# 03_MCU.net
KiCad netlist of a schematic drawn in Altium Designer
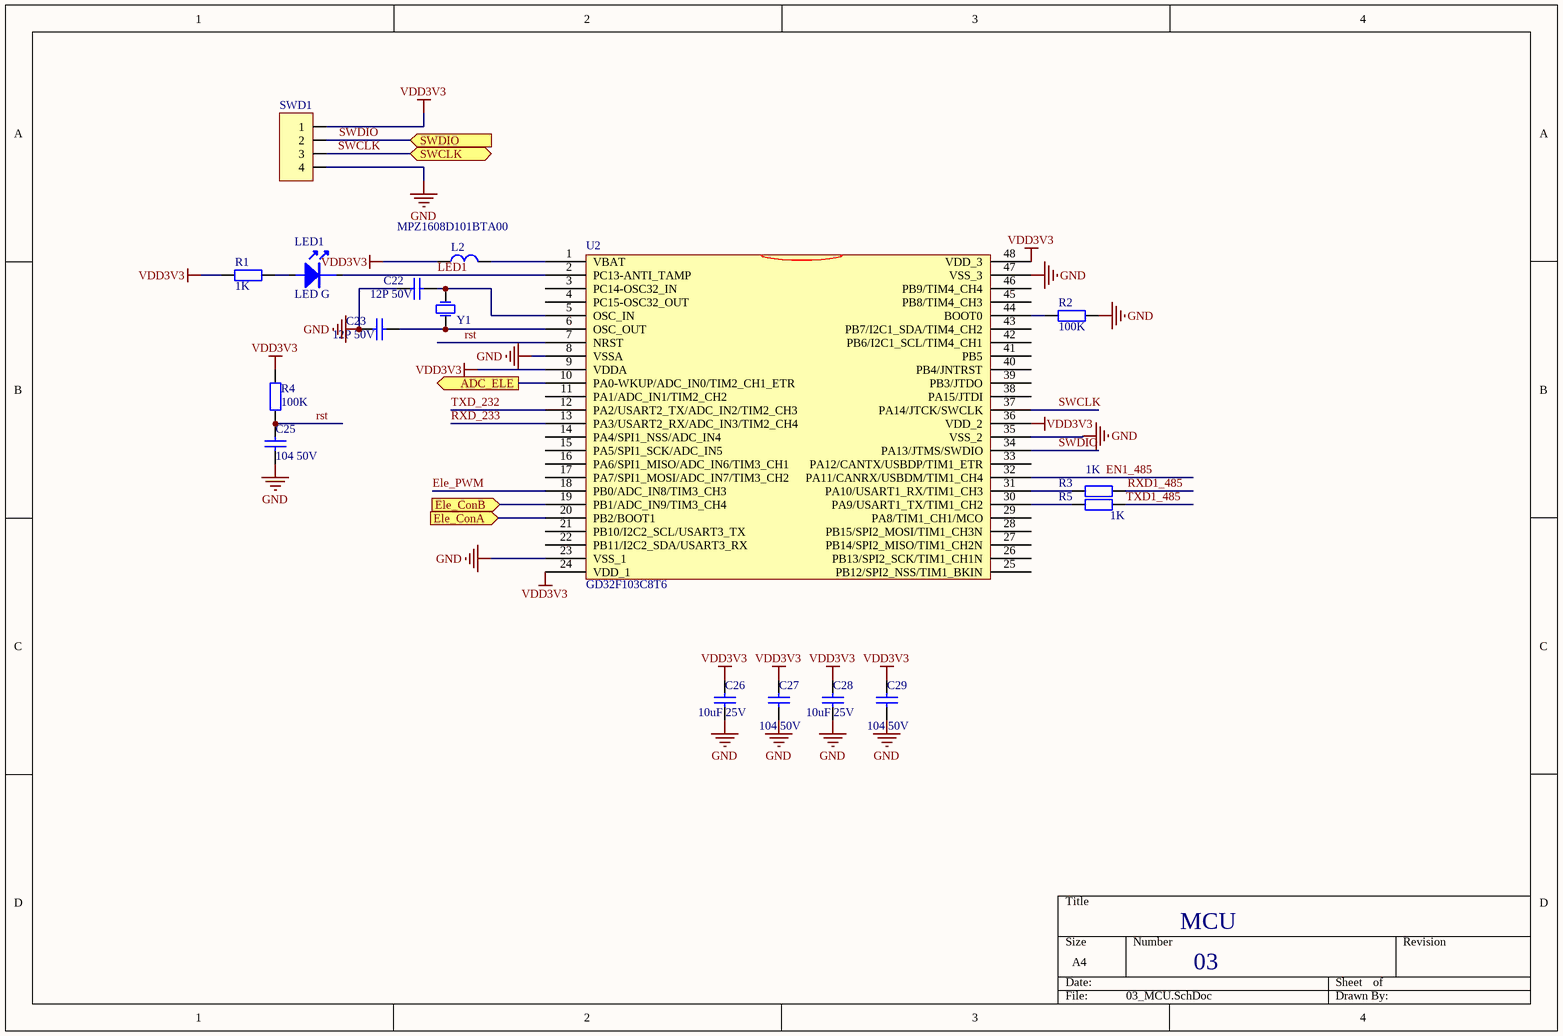
[diagram p0: 03_MCU.SchDoc]

(export (version "E")
  (design (tool "Eeschema 10.0.6"))
  (components
    (comp (ref "C22")
      (value "12P 50V")
      (footprint "SMD-0603C")
      (description "贴片电容 5%")
      (libsource (lib "XiaoyI") (part "CAP4"))
    )
    (comp (ref "C23")
      (value "12P 50V")
      (footprint "SMD-0603C")
      (description "贴片电容 5%")
      (libsource (lib "XiaoyI") (part "CAP4"))
    )
    (comp (ref "C25")
      (value "104 50V")
      (footprint "SMD-0603C")
      (description "贴片电容 20%")
      (libsource (lib "XiaoyI") (part "CAP4"))
    )
    (comp (ref "C26")
      (value "10uF 25V")
      (footprint "SMD-0805C")
      (description "贴片电容 20%")
      (libsource (lib "XiaoyI") (part "CAP4"))
    )
    (comp (ref "C27")
      (value "104 50V")
      (footprint "SMD-0603C")
      (description "贴片电容 20%")
      (libsource (lib "XiaoyI") (part "CAP4"))
    )
    (comp (ref "C28")
      (value "10uF 25V")
      (footprint "SMD-0805C")
      (description "贴片电容 20%")
      (libsource (lib "XiaoyI") (part "CAP4"))
    )
    (comp (ref "C29")
      (value "104 50V")
      (footprint "SMD-0603C")
      (description "贴片电容 20%")
      (libsource (lib "XiaoyI") (part "CAP4"))
    )
    (comp (ref "L2")
      (value "MPZ1608D101BTA00")
      (footprint "SMD-0603")
      (description "磁珠电感 100R 100MHz")
      (libsource (lib "XiaoyI") (part "CIZHU1"))
    )
    (comp (ref "LED1")
      (value "LED G")
      (footprint "SMD-0603D")
      (description "绿色普亮")
      (libsource (lib "ABB") (part "LED"))
    )
    (comp (ref "R1")
      (value "1K")
      (footprint "SMD-0603")
      (description "贴片电阻 5%")
      (libsource (lib "ABB") (part "RES0"))
    )
    (comp (ref "R2")
      (value "100K")
      (footprint "SMD-0603")
      (description "贴片电阻 5%")
      (libsource (lib "") (part "RES2_1"))
    )
    (comp (ref "R3")
      (value "1K")
      (footprint "SMD-0603")
      (description "贴片电阻 5%")
      (libsource (lib "") (part "RES2_1"))
    )
    (comp (ref "R4")
      (value "100K")
      (footprint "SMD-0603")
      (description "贴片电阻 5%")
      (libsource (lib "XiaoyI") (part "RES2"))
    )
    (comp (ref "R5")
      (value "1K")
      (footprint "SMD-0603")
      (description "贴片电阻 5%")
      (libsource (lib "") (part "RES2_1"))
    )
    (comp (ref "SWD1")
      (value "SIP-4 (NC)")
      (footprint "SIP-4")
      (description "ISP 下载")
      (libsource (lib "XiaoyI") (part "SIP-4"))
    )
    (comp (ref "U2")
      (value "GD32F103C8T6")
      (footprint "LQFP48")
      (libsource (lib "stm32") (part "STM32F103C6"))
    )
    (comp (ref "Y1")
      (value "8MHz")
      (footprint "XTAL-3225-2")
      (description "3225 贴片晶振")
      (libsource (lib "XiaoyI") (part "XTAL"))
    )
  )
  (nets
    (net (code "1") (name "/ADC_ELE") (class "Default")
      (node (ref "U2") (pin "10") (pinfunction "PA0-WKUP/ADC_IN0/TIM2_CH1_ETR_10") (pintype "passive"))
    )
    (net (code "2") (name "/EN1_485") (class "Default")
      (node (ref "U2") (pin "32") (pinfunction "PA11/CANRX/USBDM/TIM1_CH4_32") (pintype "passive"))
    )
    (net (code "3") (name "/Ele_ConA") (class "Default")
      (node (ref "U2") (pin "20") (pinfunction "PB2/BOOT1_20") (pintype "passive"))
    )
    (net (code "4") (name "/Ele_ConB") (class "Default")
      (node (ref "U2") (pin "19") (pinfunction "PB1/ADC_IN9/TIM3_CH4_19") (pintype "passive"))
    )
    (net (code "5") (name "/Ele_PWM") (class "Default")
      (node (ref "U2") (pin "18") (pinfunction "PB0/ADC_IN8/TIM3_CH3_18") (pintype "passive"))
    )
    (net (code "6") (name "/LED1") (class "Default")
      (node (ref "LED1") (pin "2") (pinfunction "K_2") (pintype "passive"))
      (node (ref "U2") (pin "2") (pinfunction "PC13-ANTI_TAMP_2") (pintype "passive"))
    )
    (net (code "7") (name "/RXD1_485") (class "Default")
      (node (ref "R3") (pin "2") (pinfunction "2_2") (pintype "passive"))
    )
    (net (code "8") (name "/RXD_233") (class "Default")
      (node (ref "U2") (pin "13") (pinfunction "PA3/USART2_RX/ADC_IN3/TIM2_CH4_13") (pintype "passive"))
    )
    (net (code "9") (name "/SWCLK") (class "Default")
      (node (ref "SWD1") (pin "3") (pinfunction "3_3") (pintype "passive"))
      (node (ref "U2") (pin "37") (pinfunction "PA14/JTCK/SWCLK_37") (pintype "passive"))
    )
    (net (code "10") (name "/SWDIO") (class "Default")
      (node (ref "SWD1") (pin "2") (pinfunction "2_2") (pintype "passive"))
      (node (ref "U2") (pin "34") (pinfunction "PA13/JTMS/SWDIO_34") (pintype "passive"))
    )
    (net (code "11") (name "/TXD1_485") (class "Default")
      (node (ref "R5") (pin "2") (pinfunction "2_2") (pintype "passive"))
    )
    (net (code "12") (name "/TXD_232") (class "Default")
      (node (ref "U2") (pin "12") (pinfunction "PA2/USART2_TX/ADC_IN2/TIM2_CH3_12") (pintype "passive"))
    )
    (net (code "13") (name "/rst") (class "Default")
      (node (ref "C25") (pin "2") (pinfunction "2_2") (pintype "passive"))
      (node (ref "R4") (pin "2") (pinfunction "2_2") (pintype "passive"))
      (node (ref "U2") (pin "7") (pinfunction "NRST_7") (pintype "passive"))
    )
    (net (code "14") (name "GND") (class "Default")
      (node (ref "C22") (pin "2") (pinfunction "2_2") (pintype "passive"))
      (node (ref "C23") (pin "2") (pinfunction "2_2") (pintype "passive"))
      (node (ref "C25") (pin "1") (pinfunction "1_1") (pintype "passive"))
      (node (ref "C26") (pin "1") (pinfunction "1_1") (pintype "passive"))
      (node (ref "C27") (pin "1") (pinfunction "1_1") (pintype "passive"))
      (node (ref "C28") (pin "1") (pinfunction "1_1") (pintype "passive"))
      (node (ref "C29") (pin "1") (pinfunction "1_1") (pintype "passive"))
      (node (ref "R2") (pin "2") (pinfunction "2_2") (pintype "passive"))
      (node (ref "SWD1") (pin "4") (pinfunction "4_4") (pintype "passive"))
      (node (ref "U2") (pin "23") (pinfunction "VSS_1_23") (pintype "passive"))
      (node (ref "U2") (pin "35") (pinfunction "VSS_2_35") (pintype "passive"))
      (node (ref "U2") (pin "47") (pinfunction "VSS_3_47") (pintype "passive"))
      (node (ref "U2") (pin "8") (pinfunction "VSSA_8") (pintype "passive"))
    )
    (net (code "15") (name "Net-(LED1-A)") (class "Default")
      (node (ref "LED1") (pin "1") (pinfunction "A_1") (pintype "passive"))
      (node (ref "R1") (pin "1") (pinfunction "1_1") (pintype "passive"))
    )
    (net (code "16") (name "Net-(U2-BOOT0)") (class "Default")
      (node (ref "R2") (pin "1") (pinfunction "1_1") (pintype "passive"))
      (node (ref "U2") (pin "44") (pinfunction "BOOT0_44") (pintype "passive"))
    )
    (net (code "17") (name "Net-(U2-OSC_IN)") (class "Default")
      (node (ref "C22") (pin "1") (pinfunction "1_1") (pintype "passive"))
      (node (ref "U2") (pin "5") (pinfunction "OSC_IN_5") (pintype "passive"))
      (node (ref "Y1") (pin "1") (pinfunction "OSC1_1") (pintype "passive"))
    )
    (net (code "18") (name "Net-(U2-OSC_OUT)") (class "Default")
      (node (ref "C23") (pin "1") (pinfunction "1_1") (pintype "passive"))
      (node (ref "U2") (pin "6") (pinfunction "OSC_OUT_6") (pintype "passive"))
      (node (ref "Y1") (pin "2") (pinfunction "OSC2_2") (pintype "passive"))
    )
    (net (code "19") (name "Net-(U2-PA9{slash}USART1_TX{slash}TIM1_CH2)") (class "Default")
      (node (ref "R5") (pin "1") (pinfunction "1_1") (pintype "passive"))
      (node (ref "U2") (pin "30") (pinfunction "PA9/USART1_TX/TIM1_CH2_30") (pintype "passive"))
    )
    (net (code "20") (name "Net-(U2-PA10{slash}USART1_RX{slash}TIM1_CH3)") (class "Default")
      (node (ref "R3") (pin "1") (pinfunction "1_1") (pintype "passive"))
      (node (ref "U2") (pin "31") (pinfunction "PA10/USART1_RX/TIM1_CH3_31") (pintype "passive"))
    )
    (net (code "21") (name "Net-(U2-VBAT)") (class "Default")
      (node (ref "L2") (pin "1") (pinfunction "1_1") (pintype "passive"))
      (node (ref "U2") (pin "1") (pinfunction "VBAT_1") (pintype "passive"))
    )
    (net (code "22") (name "VDD3V3") (class "Default")
      (node (ref "C26") (pin "2") (pinfunction "2_2") (pintype "passive"))
      (node (ref "C27") (pin "2") (pinfunction "2_2") (pintype "passive"))
      (node (ref "C28") (pin "2") (pinfunction "2_2") (pintype "passive"))
      (node (ref "C29") (pin "2") (pinfunction "2_2") (pintype "passive"))
      (node (ref "L2") (pin "2") (pinfunction "2_2") (pintype "passive"))
      (node (ref "R1") (pin "2") (pinfunction "2_2") (pintype "passive"))
      (node (ref "R4") (pin "1") (pinfunction "1_1") (pintype "passive"))
      (node (ref "SWD1") (pin "1") (pinfunction "1_1") (pintype "passive"))
      (node (ref "U2") (pin "24") (pinfunction "VDD_1_24") (pintype "passive"))
      (node (ref "U2") (pin "36") (pinfunction "VDD_2_36") (pintype "passive"))
      (node (ref "U2") (pin "48") (pinfunction "VDD_3_48") (pintype "passive"))
      (node (ref "U2") (pin "9") (pinfunction "VDDA_9") (pintype "passive"))
    )
    (net (code "23") (name "unconnected-(U2-PA1{slash}ADC_IN1{slash}TIM2_CH2-Pad11)") (class "Default")
      (node (ref "U2") (pin "11") (pinfunction "PA1/ADC_IN1/TIM2_CH2_11") (pintype "passive"))
    )
    (net (code "24") (name "unconnected-(U2-PA4{slash}SPI1_NSS{slash}ADC_IN4-Pad14)") (class "Default")
      (node (ref "U2") (pin "14") (pinfunction "PA4/SPI1_NSS/ADC_IN4_14") (pintype "passive"))
    )
    (net (code "25") (name "unconnected-(U2-PA5{slash}SPI1_SCK{slash}ADC_IN5-Pad15)") (class "Default")
      (node (ref "U2") (pin "15") (pinfunction "PA5/SPI1_SCK/ADC_IN5_15") (pintype "passive"))
    )
    (net (code "26") (name "unconnected-(U2-PA6{slash}SPI1_MISO{slash}ADC_IN6{slash}TIM3_CH1-Pad16)") (class "Default")
      (node (ref "U2") (pin "16") (pinfunction "PA6/SPI1_MISO/ADC_IN6/TIM3_CH1_16") (pintype "passive"))
    )
    (net (code "27") (name "unconnected-(U2-PA7{slash}SPI1_MOSI{slash}ADC_IN7{slash}TIM3_CH2-Pad17)") (class "Default")
      (node (ref "U2") (pin "17") (pinfunction "PA7/SPI1_MOSI/ADC_IN7/TIM3_CH2_17") (pintype "passive"))
    )
    (net (code "28") (name "unconnected-(U2-PA8{slash}TIM1_CH1{slash}MCO-Pad29)") (class "Default")
      (node (ref "U2") (pin "29") (pinfunction "PA8/TIM1_CH1/MCO_29") (pintype "passive"))
    )
    (net (code "29") (name "unconnected-(U2-PA12{slash}CANTX{slash}USBDP{slash}TIM1_ETR-Pad33)") (class "Default")
      (node (ref "U2") (pin "33") (pinfunction "PA12/CANTX/USBDP/TIM1_ETR_33") (pintype "passive"))
    )
    (net (code "30") (name "unconnected-(U2-PA15{slash}JTDI-Pad38)") (class "Default")
      (node (ref "U2") (pin "38") (pinfunction "PA15/JTDI_38") (pintype "passive"))
    )
    (net (code "31") (name "unconnected-(U2-PB3{slash}JTDO-Pad39)") (class "Default")
      (node (ref "U2") (pin "39") (pinfunction "PB3/JTDO_39") (pintype "passive"))
    )
    (net (code "32") (name "unconnected-(U2-PB4{slash}JNTRST-Pad40)") (class "Default")
      (node (ref "U2") (pin "40") (pinfunction "PB4/JNTRST_40") (pintype "passive"))
    )
    (net (code "33") (name "unconnected-(U2-PB5-Pad41)") (class "Default")
      (node (ref "U2") (pin "41") (pinfunction "PB5_41") (pintype "passive"))
    )
    (net (code "34") (name "unconnected-(U2-PB6{slash}I2C1_SCL{slash}TIM4_CH1-Pad42)") (class "Default")
      (node (ref "U2") (pin "42") (pinfunction "PB6/I2C1_SCL/TIM4_CH1_42") (pintype "passive"))
    )
    (net (code "35") (name "unconnected-(U2-PB7{slash}I2C1_SDA{slash}TIM4_CH2-Pad43)") (class "Default")
      (node (ref "U2") (pin "43") (pinfunction "PB7/I2C1_SDA/TIM4_CH2_43") (pintype "passive"))
    )
    (net (code "36") (name "unconnected-(U2-PB8{slash}TIM4_CH3-Pad45)") (class "Default")
      (node (ref "U2") (pin "45") (pinfunction "PB8/TIM4_CH3_45") (pintype "passive"))
    )
    (net (code "37") (name "unconnected-(U2-PB9{slash}TIM4_CH4-Pad46)") (class "Default")
      (node (ref "U2") (pin "46") (pinfunction "PB9/TIM4_CH4_46") (pintype "passive"))
    )
    (net (code "38") (name "unconnected-(U2-PB10{slash}I2C2_SCL{slash}USART3_TX-Pad21)") (class "Default")
      (node (ref "U2") (pin "21") (pinfunction "PB10/I2C2_SCL/USART3_TX_21") (pintype "passive"))
    )
    (net (code "39") (name "unconnected-(U2-PB11{slash}I2C2_SDA{slash}USART3_RX-Pad22)") (class "Default")
      (node (ref "U2") (pin "22") (pinfunction "PB11/I2C2_SDA/USART3_RX_22") (pintype "passive"))
    )
    (net (code "40") (name "unconnected-(U2-PB12{slash}SPI2_NSS{slash}TIM1_BKIN-Pad25)") (class "Default")
      (node (ref "U2") (pin "25") (pinfunction "PB12/SPI2_NSS/TIM1_BKIN_25") (pintype "passive"))
    )
    (net (code "41") (name "unconnected-(U2-PB13{slash}SPI2_SCK{slash}TIM1_CH1N-Pad26)") (class "Default")
      (node (ref "U2") (pin "26") (pinfunction "PB13/SPI2_SCK/TIM1_CH1N_26") (pintype "passive"))
    )
    (net (code "42") (name "unconnected-(U2-PB14{slash}SPI2_MISO{slash}TIM1_CH2N-Pad27)") (class "Default")
      (node (ref "U2") (pin "27") (pinfunction "PB14/SPI2_MISO/TIM1_CH2N_27") (pintype "passive"))
    )
    (net (code "43") (name "unconnected-(U2-PB15{slash}SPI2_MOSI{slash}TIM1_CH3N-Pad28)") (class "Default")
      (node (ref "U2") (pin "28") (pinfunction "PB15/SPI2_MOSI/TIM1_CH3N_28") (pintype "passive"))
    )
    (net (code "44") (name "unconnected-(U2-PC14-OSC32_IN-Pad3)") (class "Default")
      (node (ref "U2") (pin "3") (pinfunction "PC14-OSC32_IN_3") (pintype "passive"))
    )
    (net (code "45") (name "unconnected-(U2-PC15-OSC32_OUT-Pad4)") (class "Default")
      (node (ref "U2") (pin "4") (pinfunction "PC15-OSC32_OUT_4") (pintype "passive"))
    )
  )
)
